# Power_Servo_Connections.net
KiCad netlist of a schematic drawn in Altium Designer
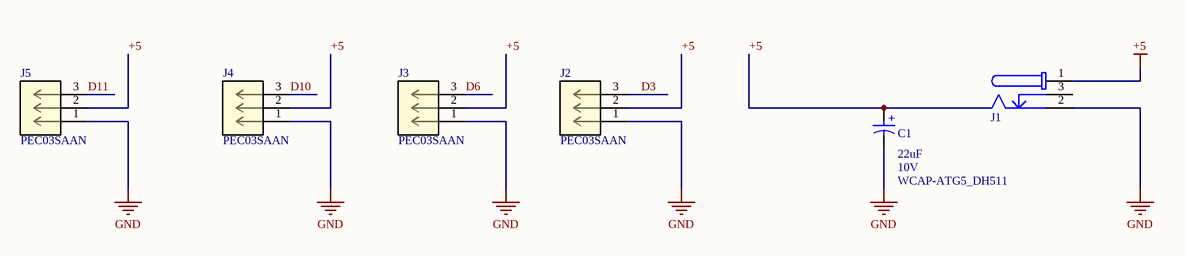
[diagram p0: Power + Servo Connections.SchDoc]

(export (version "E")
  (design (tool "Eeschema 10.0.6"))
  (components
    (comp (ref "C1")
      (value "22µF")
      (footprint "WCAP-ATG5_D5H11")
      (description "WCAP-ATG5 Aluminum Electrolytic Capacitor, Radial, THT, D5 x H11mm, 22µF, 10V")
      (fields
        (field (name "MANUFACTURER PART NUMBER") "860020272001")
        (field (name "MANUFACTURER") "Wurth Elektronik")
      )
      (libsource (lib "Schlib1") (part "860020272001"))
    )
    (comp (ref "J1")
      (value "694102107102")
      (footprint "694102107102")
      (description "WR-DC DC Power Jack Connector, Male, Right Angled, 18V, 5A")
      (fields (field (name "MANUFACTURER") "Wurth Elektronik"))
      (libsource (lib "Altium_WR-DC_rev22a") (part "694102107102"))
    )
    (comp (ref "J2")
      (value "PEC03SAAN")
      (footprint "CONN_PEC03SAAN_SUL")
      (description "EVKIT PART-CONNECTOR; MALE; THROUGH HOLE; BREAKAWAY;")
      (fields (field (name "COPYRIGHT") "Copyright (C) 2026 Ultra Librarian. All rights reserved."))
      (libsource (lib "Schlib1") (part "PEC03SAAN"))
    )
    (comp (ref "J3")
      (value "PEC03SAAN")
      (footprint "CONN_PEC03SAAN_SUL")
      (description "EVKIT PART-CONNECTOR; MALE; THROUGH HOLE; BREAKAWAY;")
      (fields (field (name "COPYRIGHT") "Copyright (C) 2026 Ultra Librarian. All rights reserved."))
      (libsource (lib "Schlib1") (part "PEC03SAAN"))
    )
    (comp (ref "J4")
      (value "PEC03SAAN")
      (footprint "CONN_PEC03SAAN_SUL")
      (description "EVKIT PART-CONNECTOR; MALE; THROUGH HOLE; BREAKAWAY;")
      (fields (field (name "COPYRIGHT") "Copyright (C) 2026 Ultra Librarian. All rights reserved."))
      (libsource (lib "Schlib1") (part "PEC03SAAN"))
    )
    (comp (ref "J5")
      (value "PEC03SAAN")
      (footprint "CONN_PEC03SAAN_SUL")
      (description "EVKIT PART-CONNECTOR; MALE; THROUGH HOLE; BREAKAWAY;")
      (fields (field (name "COPYRIGHT") "Copyright (C) 2026 Ultra Librarian. All rights reserved."))
      (libsource (lib "Schlib1") (part "PEC03SAAN"))
    )
  )
  (nets
    (net (code "1") (name "+5") (class "Default")
      (node (ref "C1") (pin "1") (pinfunction "P_1") (pintype "passive"))
      (node (ref "J1") (pin "1") (pinfunction "1_1") (pintype "passive"))
      (node (ref "J2") (pin "2") (pinfunction "2_2") (pintype "passive"))
      (node (ref "J3") (pin "2") (pinfunction "2_2") (pintype "passive"))
      (node (ref "J4") (pin "2") (pinfunction "2_2") (pintype "passive"))
      (node (ref "J5") (pin "2") (pinfunction "2_2") (pintype "passive"))
    )
    (net (code "2") (name "/D3") (class "Default")
      (node (ref "J2") (pin "3") (pinfunction "3_3") (pintype "passive"))
    )
    (net (code "3") (name "/D6") (class "Default")
      (node (ref "J3") (pin "3") (pinfunction "3_3") (pintype "passive"))
    )
    (net (code "4") (name "/D10") (class "Default")
      (node (ref "J4") (pin "3") (pinfunction "3_3") (pintype "passive"))
    )
    (net (code "5") (name "/D11") (class "Default")
      (node (ref "J5") (pin "3") (pinfunction "3_3") (pintype "passive"))
    )
    (net (code "6") (name "GND") (class "Default")
      (node (ref "C1") (pin "2") (pinfunction "N_2") (pintype "passive"))
      (node (ref "J1") (pin "2") (pinfunction "2_2") (pintype "passive"))
      (node (ref "J2") (pin "1") (pinfunction "1_1") (pintype "passive"))
      (node (ref "J3") (pin "1") (pinfunction "1_1") (pintype "passive"))
      (node (ref "J4") (pin "1") (pinfunction "1_1") (pintype "passive"))
      (node (ref "J5") (pin "1") (pinfunction "1_1") (pintype "passive"))
    )
    (net (code "7") (name "unconnected-(J1-Pad3)") (class "Default")
      (node (ref "J1") (pin "3") (pinfunction "3_3") (pintype "passive"))
    )
  )
)
